# primary_LTC.net
KiCad netlist of a schematic drawn in Altium Designer
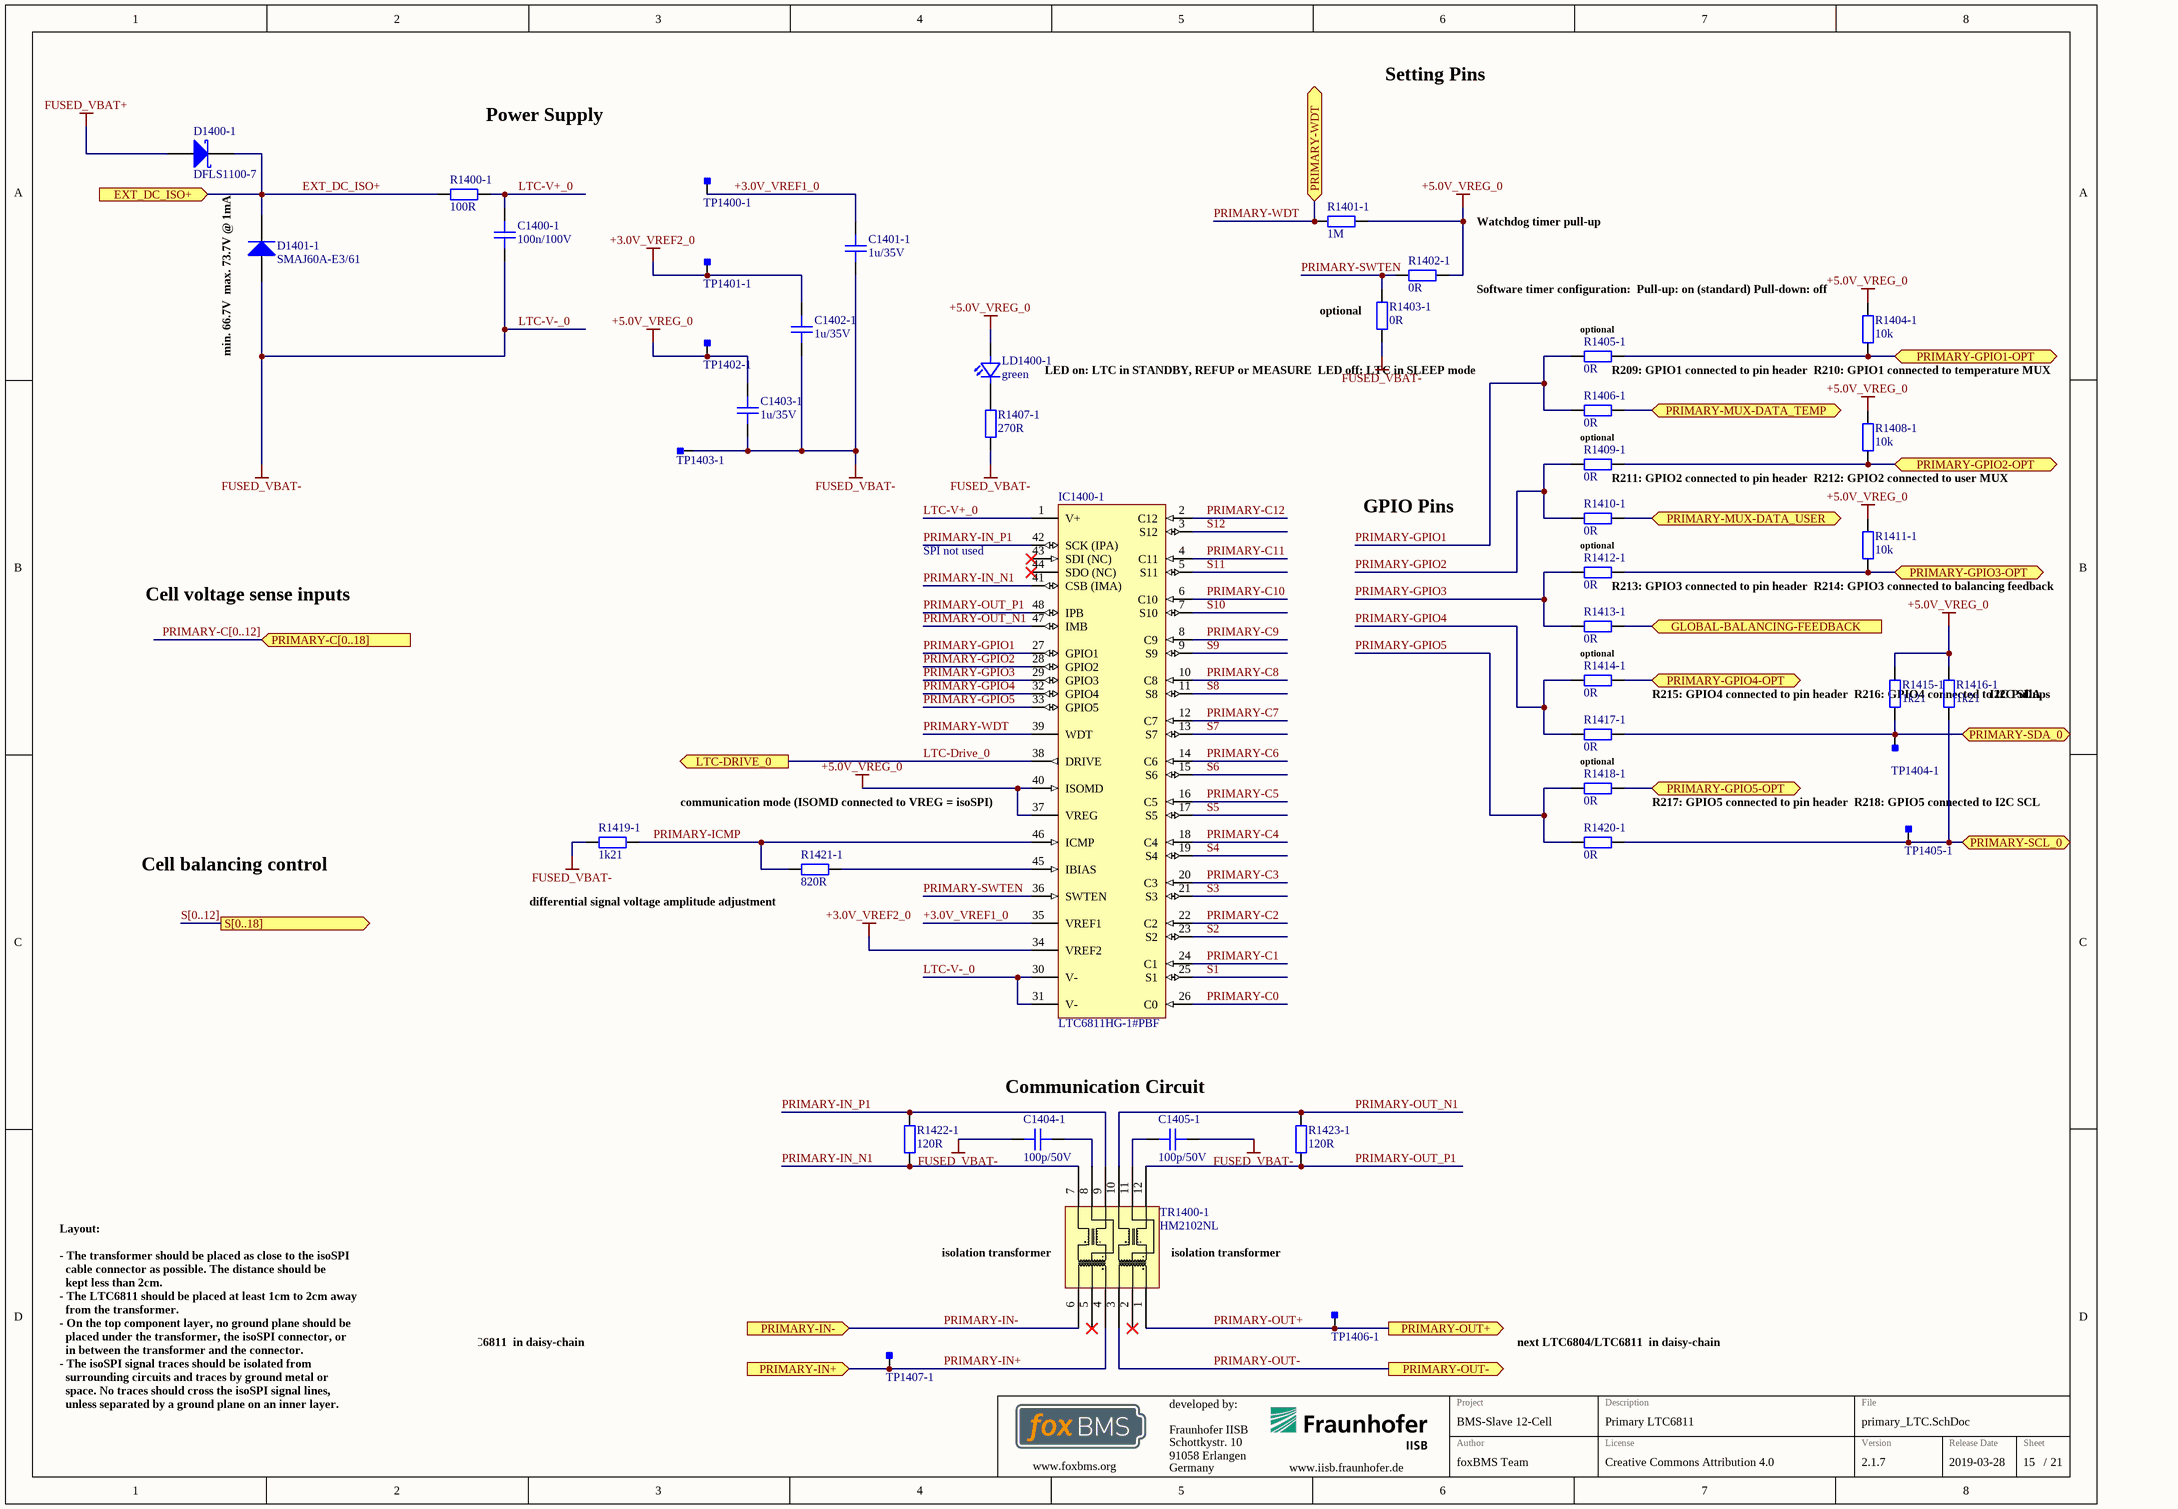
[diagram p0: primary_LTC.SchDoc]

(export (version "E")
  (design (tool "Eeschema 10.0.6"))
  (components
    (comp (ref "C1400-1")
      (value "100n/100V")
      (footprint "CAPC2012X14N")
      (description "MLCC")
      (fields (field (name "PART NUMBER") "gen_C_ceramic_100n_100V_X7R_0805"))
      (libsource (lib "OE750") (part "C"))
    )
    (comp (ref "C1401-1")
      (value "1u/35V")
      (footprint "CAPC1608X08N")
      (description "MLCC")
      (fields (field (name "PART NUMBER") "gen_C_ceramic_1u_35V_X7R_0603"))
      (libsource (lib "OE750") (part "C"))
    )
    (comp (ref "C1402-1")
      (value "1u/35V")
      (footprint "CAPC1608X08N")
      (description "MLCC")
      (fields (field (name "PART NUMBER") "gen_C_ceramic_1u_35V_X7R_0603"))
      (libsource (lib "OE750") (part "C"))
    )
    (comp (ref "C1403-1")
      (value "1u/35V")
      (footprint "CAPC1608X08N")
      (description "MLCC")
      (fields (field (name "PART NUMBER") "gen_C_ceramic_1u_35V_X7R_0603"))
      (libsource (lib "OE750") (part "C"))
    )
    (comp (ref "C1404-1")
      (value "100p/50V")
      (footprint "CAPC1608X08N")
      (description "MLCC")
      (fields (field (name "PART NUMBER") "gen_C_ceramic_100p_50V_C0G_0603"))
      (libsource (lib "OE750") (part "C"))
    )
    (comp (ref "C1405-1")
      (value "100p/50V")
      (footprint "CAPC1608X08N")
      (description "MLCC")
      (fields (field (name "PART NUMBER") "gen_C_ceramic_100p_50V_C0G_0603"))
      (libsource (lib "OE750") (part "C"))
    )
    (comp (ref "D1400-1")
      (value "DFLS1100-7")
      (footprint "DIOD-POWERDI123-2_V")
      (fields (field (name "MANUFACTURER") "Diodes Inc"))
      (libsource (lib "Altium Content Vault") (part "DSKY-AK-2"))
    )
    (comp (ref "D1401-1")
      (value "SMAJ60A-E3/61")
      (footprint "VISH-DO-214AC-2_N")
      (fields (field (name "MANUFACTURER") "Vishay Semiconductor"))
      (libsource (lib "Altium Content Vault") (part "VISH-K1A2-2"))
    )
    (comp (ref "IC1400-1")
      (value "LTC6811HG-1#PBF")
      (footprint "LT-G-48_L")
      (description "Multicell Battery Monitor, 60 V Vin MAX, 48-pin SOP (G-48), -40 to 125 degC, Pb-Free")
      (fields (field (name "MANUFACTURER") "Linear Technology"))
      (libsource (lib "OE750") (part "LTC6811HG-1#PBF"))
    )
    (comp (ref "LD1400-1")
      (value "green")
      (footprint "LEDC1608X07N")
      (description "LED")
      (fields (field (name "PART NUMBER") "gen_LED_0603_green"))
      (libsource (lib "OE750") (part "D_LED"))
    )
    (comp (ref "R1400-1")
      (value "100R")
      (footprint "RESC2012X05N")
      (description "SMD Resistor 100R 0805")
      (fields (field (name "PART NUMBER") "gen_R_100R_0805") (field (name "TOLERANCE") "1%"))
      (libsource (lib "OE750") (part "R"))
    )
    (comp (ref "R1401-1")
      (value "1M")
      (footprint "RESC1608X05N")
      (description "SMD Resistor 1M 0603")
      (fields (field (name "PART NUMBER") "gen_R_1M_0603") (field (name "TOLERANCE") "1%"))
      (libsource (lib "OE750") (part "R"))
    )
    (comp (ref "R1402-1")
      (value "0R")
      (footprint "RESC1608X05N")
      (description "SMD Resistor 0R 0603")
      (fields (field (name "PART NUMBER") "gen_R_0R_0603") (field (name "POWER") "0.1W"))
      (libsource (lib "OE750") (part "R"))
    )
    (comp (ref "R1403-1")
      (value "0R")
      (footprint "RESC1608X05N")
      (description "SMD Resistor 0R 0603")
      (fields (field (name "PART NUMBER") "gen_R_0R_0603") (field (name "POWER") "0.1W"))
      (libsource (lib "OE750") (part "R"))
    )
    (comp (ref "R1404-1")
      (value "10k")
      (footprint "RESC1608X05N")
      (description "SMD Resistor 10k 0603")
      (fields (field (name "PART NUMBER") "gen_R_10k_0603") (field (name "TOLERANCE") "1%"))
      (libsource (lib "OE750") (part "R"))
    )
    (comp (ref "R1405-1")
      (value "0R")
      (footprint "RESC1608X05N")
      (description "SMD Resistor 0R 0603")
      (fields (field (name "PART NUMBER") "gen_R_0R_0603") (field (name "POWER") "0.1W"))
      (libsource (lib "OE750") (part "R"))
    )
    (comp (ref "R1406-1")
      (value "0R")
      (footprint "RESC1608X05N")
      (description "SMD Resistor 0R 0603")
      (fields (field (name "PART NUMBER") "gen_R_0R_0603") (field (name "POWER") "0.1W"))
      (libsource (lib "OE750") (part "R"))
    )
    (comp (ref "R1407-1")
      (value "270R")
      (footprint "RESC1608X05N")
      (description "SMD Resistor 270R 0603")
      (fields (field (name "PART NUMBER") "gen_R_270R_0603") (field (name "TOLERANCE") "1%"))
      (libsource (lib "OE750") (part "R"))
    )
    (comp (ref "R1408-1")
      (value "10k")
      (footprint "RESC1608X05N")
      (description "SMD Resistor 10k 0603")
      (fields (field (name "PART NUMBER") "gen_R_10k_0603") (field (name "TOLERANCE") "1%"))
      (libsource (lib "OE750") (part "R"))
    )
    (comp (ref "R1409-1")
      (value "0R")
      (footprint "RESC1608X05N")
      (description "SMD Resistor 0R 0603")
      (fields (field (name "PART NUMBER") "gen_R_0R_0603") (field (name "POWER") "0.1W"))
      (libsource (lib "OE750") (part "R"))
    )
    (comp (ref "R1410-1")
      (value "0R")
      (footprint "RESC1608X05N")
      (description "SMD Resistor 0R 0603")
      (fields (field (name "PART NUMBER") "gen_R_0R_0603") (field (name "POWER") "0.1W"))
      (libsource (lib "OE750") (part "R"))
    )
    (comp (ref "R1411-1")
      (value "10k")
      (footprint "RESC1608X05N")
      (description "SMD Resistor 10k 0603")
      (fields (field (name "PART NUMBER") "gen_R_10k_0603") (field (name "TOLERANCE") "1%"))
      (libsource (lib "OE750") (part "R"))
    )
    (comp (ref "R1412-1")
      (value "0R")
      (footprint "RESC1608X05N")
      (description "SMD Resistor 0R 0603")
      (fields (field (name "PART NUMBER") "gen_R_0R_0603") (field (name "POWER") "0.1W"))
      (libsource (lib "OE750") (part "R"))
    )
    (comp (ref "R1413-1")
      (value "0R")
      (footprint "RESC1608X05N")
      (description "SMD Resistor 0R 0603")
      (fields (field (name "PART NUMBER") "gen_R_0R_0603") (field (name "POWER") "0.1W"))
      (libsource (lib "OE750") (part "R"))
    )
    (comp (ref "R1414-1")
      (value "0R")
      (footprint "RESC1608X05N")
      (description "SMD Resistor 0R 0603")
      (fields (field (name "PART NUMBER") "gen_R_0R_0603") (field (name "POWER") "0.1W"))
      (libsource (lib "OE750") (part "R"))
    )
    (comp (ref "R1415-1")
      (value "1k21")
      (footprint "RESC1608X05N")
      (description "SMD Resistor 1k21 0603")
      (fields (field (name "PART NUMBER") "gen_R_1k21_0603") (field (name "TOLERANCE") "1%"))
      (libsource (lib "OE750") (part "R"))
    )
    (comp (ref "R1416-1")
      (value "1k21")
      (footprint "RESC1608X05N")
      (description "SMD Resistor 1k21 0603")
      (fields (field (name "PART NUMBER") "gen_R_1k21_0603") (field (name "TOLERANCE") "1%"))
      (libsource (lib "OE750") (part "R"))
    )
    (comp (ref "R1417-1")
      (value "0R")
      (footprint "RESC1608X05N")
      (description "SMD Resistor 0R 0603")
      (fields (field (name "PART NUMBER") "gen_R_0R_0603") (field (name "POWER") "0.1W"))
      (libsource (lib "OE750") (part "R"))
    )
    (comp (ref "R1418-1")
      (value "0R")
      (footprint "RESC1608X05N")
      (description "SMD Resistor 0R 0603")
      (fields (field (name "PART NUMBER") "gen_R_0R_0603") (field (name "POWER") "0.1W"))
      (libsource (lib "OE750") (part "R"))
    )
    (comp (ref "R1419-1")
      (value "1k21")
      (footprint "RESC1608X05N")
      (description "SMD Resistor 1k21 0603")
      (fields (field (name "PART NUMBER") "gen_R_1k21_0603") (field (name "TOLERANCE") "1%"))
      (libsource (lib "OE750") (part "R"))
    )
    (comp (ref "R1420-1")
      (value "0R")
      (footprint "RESC1608X05N")
      (description "SMD Resistor 0R 0603")
      (fields (field (name "PART NUMBER") "gen_R_0R_0603") (field (name "POWER") "0.1W"))
      (libsource (lib "OE750") (part "R"))
    )
    (comp (ref "R1421-1")
      (value "820R")
      (footprint "RESC1608X05N")
      (description "SMD Resistor 820R 0603")
      (fields (field (name "PART NUMBER") "gen_R_820R_0603") (field (name "TOLERANCE") "1%"))
      (libsource (lib "OE750") (part "R"))
    )
    (comp (ref "R1422-1")
      (value "120R")
      (footprint "RESC1608X05N")
      (description "SMD Resistor 120R 0603")
      (fields (field (name "PART NUMBER") "gen_R_120R_0603") (field (name "TOLERANCE") "1%"))
      (libsource (lib "OE750") (part "R"))
    )
    (comp (ref "R1423-1")
      (value "120R")
      (footprint "RESC1608X05N")
      (description "SMD Resistor 120R 0603")
      (fields (field (name "PART NUMBER") "gen_R_120R_0603") (field (name "TOLERANCE") "1%"))
      (libsource (lib "OE750") (part "R"))
    )
    (comp (ref "TP1400-1")
      (value "Testpoint_Square")
      (footprint "Testpoint_S1")
      (description "Testpoint, square")
      (libsource (lib "OE750") (part "Testpoint_Square"))
    )
    (comp (ref "TP1401-1")
      (value "Testpoint_Square")
      (footprint "Testpoint_S1")
      (description "Testpoint, square")
      (libsource (lib "OE750") (part "Testpoint_Square"))
    )
    (comp (ref "TP1402-1")
      (value "Testpoint_Square")
      (footprint "Testpoint_S1")
      (description "Testpoint, square")
      (libsource (lib "OE750") (part "Testpoint_Square"))
    )
    (comp (ref "TP1403-1")
      (value "Testpoint_Square")
      (footprint "Testpoint_S1")
      (description "Testpoint, square")
      (libsource (lib "OE750") (part "Testpoint_Square"))
    )
    (comp (ref "TP1404-1")
      (value "Testpoint_Square")
      (footprint "Testpoint_S1")
      (description "Testpoint, square")
      (libsource (lib "OE750") (part "Testpoint_Square"))
    )
    (comp (ref "TP1405-1")
      (value "Testpoint_Square")
      (footprint "Testpoint_S1")
      (description "Testpoint, square")
      (libsource (lib "OE750") (part "Testpoint_Square"))
    )
    (comp (ref "TP1406-1")
      (value "Testpoint_Square")
      (footprint "Testpoint_S1")
      (description "Testpoint, square")
      (libsource (lib "OE750") (part "Testpoint_Square"))
    )
    (comp (ref "TP1407-1")
      (value "Testpoint_Square")
      (footprint "Testpoint_S1")
      (description "Testpoint, square")
      (libsource (lib "OE750") (part "Testpoint_Square"))
    )
    (comp (ref "TR1400-1")
      (value "HM2102NL")
      (footprint "HM2102NL")
      (description "Pulse HM2102NL BMS Transformer")
      (fields (field (name "MANUFACTURER") "Pulse"))
      (libsource (lib "OE750") (part "HM2102NL"))
    )
  )
  (nets
    (net (code "2") (name "+3.0V_VREF2_0") (class "Default")
      (node (ref "C1402-1") (pin "2") (pinfunction "2_2") (pintype "passive"))
      (node (ref "IC1400-1") (pin "34") (pinfunction "VREF2_34") (pintype "passive"))
      (node (ref "TP1401-1") (pin "1") (pinfunction "1_1") (pintype "passive"))
    )
    (net (code "3") (name "+5.0V_VREG_0") (class "Default")
      (node (ref "C1403-1") (pin "2") (pinfunction "2_2") (pintype "passive"))
      (node (ref "IC1400-1") (pin "37") (pinfunction "VREG_37") (pintype "power_in"))
      (node (ref "IC1400-1") (pin "40") (pinfunction "ISOMD_40") (pintype "input"))
      (node (ref "LD1400-1") (pin "2") (pinfunction "A_2") (pintype "passive"))
      (node (ref "R1401-1") (pin "2") (pinfunction "2_2") (pintype "passive"))
      (node (ref "R1402-1") (pin "2") (pinfunction "2_2") (pintype "passive"))
      (node (ref "R1404-1") (pin "2") (pinfunction "2_2") (pintype "passive"))
      (node (ref "R1408-1") (pin "2") (pinfunction "2_2") (pintype "passive"))
      (node (ref "R1411-1") (pin "2") (pinfunction "2_2") (pintype "passive"))
      (node (ref "R1415-1") (pin "2") (pinfunction "2_2") (pintype "passive"))
      (node (ref "R1416-1") (pin "2") (pinfunction "2_2") (pintype "passive"))
      (node (ref "TP1402-1") (pin "1") (pinfunction "1_1") (pintype "passive"))
    )
    (net (code "4") (name "/+3.0V_VREF1_0") (class "Default")
      (node (ref "C1401-1") (pin "2") (pinfunction "2_2") (pintype "passive"))
      (node (ref "IC1400-1") (pin "35") (pinfunction "VREF1_35") (pintype "passive"))
      (node (ref "TP1400-1") (pin "1") (pinfunction "1_1") (pintype "passive"))
    )
    (net (code "5") (name "/EXT_DC_ISO+") (class "Default")
      (node (ref "D1400-1") (pin "2") (pinfunction "K_2") (pintype "passive"))
      (node (ref "D1401-1") (pin "1") (pinfunction "K_1") (pintype "passive"))
      (node (ref "R1400-1") (pin "1") (pinfunction "1_1") (pintype "passive"))
    )
    (net (code "6") (name "/GLOBAL-BALANCING-FEEDBACK") (class "Default")
      (node (ref "R1413-1") (pin "1") (pinfunction "1_1") (pintype "passive"))
    )
    (net (code "7") (name "/LTC-Drive_0") (class "Default")
      (node (ref "IC1400-1") (pin "38") (pinfunction "DRIVE_38") (pintype "output"))
    )
    (net (code "8") (name "/LTC-V+_0") (class "Default")
      (node (ref "C1400-1") (pin "1") (pinfunction "1_1") (pintype "passive"))
      (node (ref "IC1400-1") (pin "1") (pinfunction "V+_1") (pintype "power_in"))
      (node (ref "R1400-1") (pin "2") (pinfunction "2_2") (pintype "passive"))
    )
    (net (code "9") (name "/PRIMARY-C0") (class "Default")
      (node (ref "IC1400-1") (pin "26") (pinfunction "C0_26") (pintype "input"))
    )
    (net (code "10") (name "/PRIMARY-C1") (class "Default")
      (node (ref "IC1400-1") (pin "24") (pinfunction "C1_24") (pintype "input"))
    )
    (net (code "11") (name "/PRIMARY-C2") (class "Default")
      (node (ref "IC1400-1") (pin "22") (pinfunction "C2_22") (pintype "input"))
    )
    (net (code "12") (name "/PRIMARY-C3") (class "Default")
      (node (ref "IC1400-1") (pin "20") (pinfunction "C3_20") (pintype "input"))
    )
    (net (code "13") (name "/PRIMARY-C4") (class "Default")
      (node (ref "IC1400-1") (pin "18") (pinfunction "C4_18") (pintype "input"))
    )
    (net (code "14") (name "/PRIMARY-C5") (class "Default")
      (node (ref "IC1400-1") (pin "16") (pinfunction "C5_16") (pintype "input"))
    )
    (net (code "15") (name "/PRIMARY-C6") (class "Default")
      (node (ref "IC1400-1") (pin "14") (pinfunction "C6_14") (pintype "input"))
    )
    (net (code "16") (name "/PRIMARY-C7") (class "Default")
      (node (ref "IC1400-1") (pin "12") (pinfunction "C7_12") (pintype "input"))
    )
    (net (code "17") (name "/PRIMARY-C8") (class "Default")
      (node (ref "IC1400-1") (pin "10") (pinfunction "C8_10") (pintype "input"))
    )
    (net (code "18") (name "/PRIMARY-C9") (class "Default")
      (node (ref "IC1400-1") (pin "8") (pinfunction "C9_8") (pintype "input"))
    )
    (net (code "19") (name "/PRIMARY-C10") (class "Default")
      (node (ref "IC1400-1") (pin "6") (pinfunction "C10_6") (pintype "input"))
    )
    (net (code "20") (name "/PRIMARY-C11") (class "Default")
      (node (ref "IC1400-1") (pin "4") (pinfunction "C11_4") (pintype "input"))
    )
    (net (code "21") (name "/PRIMARY-C12") (class "Default")
      (node (ref "IC1400-1") (pin "2") (pinfunction "C12_2") (pintype "input"))
    )
    (net (code "23") (name "/PRIMARY-GPIO1") (class "Default")
      (node (ref "IC1400-1") (pin "27") (pinfunction "GPIO1_27") (pintype "bidirectional"))
      (node (ref "R1405-1") (pin "2") (pinfunction "2_2") (pintype "passive"))
      (node (ref "R1406-1") (pin "2") (pinfunction "2_2") (pintype "passive"))
    )
    (net (code "24") (name "/PRIMARY-GPIO1-OPT") (class "Default")
      (node (ref "R1404-1") (pin "1") (pinfunction "1_1") (pintype "passive"))
      (node (ref "R1405-1") (pin "1") (pinfunction "1_1") (pintype "passive"))
    )
    (net (code "25") (name "/PRIMARY-GPIO2") (class "Default")
      (node (ref "IC1400-1") (pin "28") (pinfunction "GPIO2_28") (pintype "bidirectional"))
      (node (ref "R1409-1") (pin "2") (pinfunction "2_2") (pintype "passive"))
      (node (ref "R1410-1") (pin "2") (pinfunction "2_2") (pintype "passive"))
    )
    (net (code "26") (name "/PRIMARY-GPIO2-OPT") (class "Default")
      (node (ref "R1408-1") (pin "1") (pinfunction "1_1") (pintype "passive"))
      (node (ref "R1409-1") (pin "1") (pinfunction "1_1") (pintype "passive"))
    )
    (net (code "27") (name "/PRIMARY-GPIO3") (class "Default")
      (node (ref "IC1400-1") (pin "29") (pinfunction "GPIO3_29") (pintype "bidirectional"))
      (node (ref "R1412-1") (pin "2") (pinfunction "2_2") (pintype "passive"))
      (node (ref "R1413-1") (pin "2") (pinfunction "2_2") (pintype "passive"))
    )
    (net (code "28") (name "/PRIMARY-GPIO3-OPT") (class "Default")
      (node (ref "R1411-1") (pin "1") (pinfunction "1_1") (pintype "passive"))
      (node (ref "R1412-1") (pin "1") (pinfunction "1_1") (pintype "passive"))
    )
    (net (code "29") (name "/PRIMARY-GPIO4") (class "Default")
      (node (ref "IC1400-1") (pin "32") (pinfunction "GPIO4_32") (pintype "bidirectional"))
      (node (ref "R1414-1") (pin "2") (pinfunction "2_2") (pintype "passive"))
      (node (ref "R1417-1") (pin "2") (pinfunction "2_2") (pintype "passive"))
    )
    (net (code "30") (name "/PRIMARY-GPIO4-OPT") (class "Default")
      (node (ref "R1414-1") (pin "1") (pinfunction "1_1") (pintype "passive"))
    )
    (net (code "31") (name "/PRIMARY-GPIO5") (class "Default")
      (node (ref "IC1400-1") (pin "33") (pinfunction "GPIO5_33") (pintype "bidirectional"))
      (node (ref "R1418-1") (pin "2") (pinfunction "2_2") (pintype "passive"))
      (node (ref "R1420-1") (pin "2") (pinfunction "2_2") (pintype "passive"))
    )
    (net (code "32") (name "/PRIMARY-GPIO5-OPT") (class "Default")
      (node (ref "R1418-1") (pin "1") (pinfunction "1_1") (pintype "passive"))
    )
    (net (code "33") (name "/PRIMARY-ICMP") (class "Default")
      (node (ref "IC1400-1") (pin "46") (pinfunction "ICMP_46") (pintype "input"))
      (node (ref "R1419-1") (pin "2") (pinfunction "2_2") (pintype "passive"))
      (node (ref "R1421-1") (pin "1") (pinfunction "1_1") (pintype "passive"))
    )
    (net (code "34") (name "/PRIMARY-IN+") (class "Default")
      (node (ref "TP1407-1") (pin "1") (pinfunction "1_1") (pintype "passive"))
      (node (ref "TR1400-1") (pin "4") (pintype "passive"))
    )
    (net (code "35") (name "/PRIMARY-IN-") (class "Default")
      (node (ref "TR1400-1") (pin "6") (pintype "passive"))
    )
    (net (code "36") (name "/PRIMARY-IN_N1") (class "Default")
      (node (ref "IC1400-1") (pin "41") (pinfunction "CSB_(IMA)_41") (pintype "bidirectional"))
      (node (ref "R1422-1") (pin "2") (pinfunction "2_2") (pintype "passive"))
      (node (ref "TR1400-1") (pin "7") (pintype "passive"))
    )
    (net (code "37") (name "/PRIMARY-IN_P1") (class "Default")
      (node (ref "IC1400-1") (pin "42") (pinfunction "SCK_(IPA)_42") (pintype "bidirectional"))
      (node (ref "R1422-1") (pin "1") (pinfunction "1_1") (pintype "passive"))
      (node (ref "TR1400-1") (pin "9") (pintype "passive"))
    )
    (net (code "38") (name "/PRIMARY-MUX-DATA_TEMP") (class "Default")
      (node (ref "R1406-1") (pin "1") (pinfunction "1_1") (pintype "passive"))
    )
    (net (code "39") (name "/PRIMARY-MUX-DATA_USER") (class "Default")
      (node (ref "R1410-1") (pin "1") (pinfunction "1_1") (pintype "passive"))
    )
    (net (code "40") (name "/PRIMARY-OUT+") (class "Default")
      (node (ref "TP1406-1") (pin "1") (pinfunction "1_1") (pintype "passive"))
      (node (ref "TR1400-1") (pin "1") (pintype "passive"))
    )
    (net (code "41") (name "/PRIMARY-OUT-") (class "Default")
      (node (ref "TR1400-1") (pin "3") (pintype "passive"))
    )
    (net (code "42") (name "/PRIMARY-OUT_N1") (class "Default")
      (node (ref "IC1400-1") (pin "47") (pinfunction "IMB_47") (pintype "bidirectional"))
      (node (ref "R1423-1") (pin "2") (pinfunction "2_2") (pintype "passive"))
      (node (ref "TR1400-1") (pin "10") (pintype "passive"))
    )
    (net (code "43") (name "/PRIMARY-OUT_P1") (class "Default")
      (node (ref "IC1400-1") (pin "48") (pinfunction "IPB_48") (pintype "bidirectional"))
      (node (ref "R1423-1") (pin "1") (pinfunction "1_1") (pintype "passive"))
      (node (ref "TR1400-1") (pin "12") (pintype "passive"))
    )
    (net (code "44") (name "/PRIMARY-SCL_0") (class "Default")
      (node (ref "R1416-1") (pin "1") (pinfunction "1_1") (pintype "passive"))
      (node (ref "R1420-1") (pin "1") (pinfunction "1_1") (pintype "passive"))
      (node (ref "TP1405-1") (pin "1") (pinfunction "1_1") (pintype "passive"))
    )
    (net (code "45") (name "/PRIMARY-SDA_0") (class "Default")
      (node (ref "R1415-1") (pin "1") (pinfunction "1_1") (pintype "passive"))
      (node (ref "R1417-1") (pin "1") (pinfunction "1_1") (pintype "passive"))
      (node (ref "TP1404-1") (pin "1") (pinfunction "1_1") (pintype "passive"))
    )
    (net (code "46") (name "/PRIMARY-SWTEN") (class "Default")
      (node (ref "IC1400-1") (pin "36") (pinfunction "SWTEN_36") (pintype "input"))
      (node (ref "R1402-1") (pin "1") (pinfunction "1_1") (pintype "passive"))
      (node (ref "R1403-1") (pin "2") (pinfunction "2_2") (pintype "passive"))
    )
    (net (code "47") (name "/PRIMARY-WDT") (class "Default")
      (node (ref "IC1400-1") (pin "39") (pinfunction "WDT_39") (pintype "tri_state"))
      (node (ref "R1401-1") (pin "1") (pinfunction "1_1") (pintype "passive"))
    )
    (net (code "48") (name "/S1") (class "Default")
      (node (ref "IC1400-1") (pin "25") (pinfunction "S1_25") (pintype "bidirectional"))
    )
    (net (code "49") (name "/S2") (class "Default")
      (node (ref "IC1400-1") (pin "23") (pinfunction "S2_23") (pintype "bidirectional"))
    )
    (net (code "50") (name "/S3") (class "Default")
      (node (ref "IC1400-1") (pin "21") (pinfunction "S3_21") (pintype "bidirectional"))
    )
    (net (code "51") (name "/S4") (class "Default")
      (node (ref "IC1400-1") (pin "19") (pinfunction "S4_19") (pintype "bidirectional"))
    )
    (net (code "52") (name "/S5") (class "Default")
      (node (ref "IC1400-1") (pin "17") (pinfunction "S5_17") (pintype "bidirectional"))
    )
    (net (code "53") (name "/S6") (class "Default")
      (node (ref "IC1400-1") (pin "15") (pinfunction "S6_15") (pintype "bidirectional"))
    )
    (net (code "54") (name "/S7") (class "Default")
      (node (ref "IC1400-1") (pin "13") (pinfunction "S7_13") (pintype "bidirectional"))
    )
    (net (code "55") (name "/S8") (class "Default")
      (node (ref "IC1400-1") (pin "11") (pinfunction "S8_11") (pintype "bidirectional"))
    )
    (net (code "56") (name "/S9") (class "Default")
      (node (ref "IC1400-1") (pin "9") (pinfunction "S9_9") (pintype "bidirectional"))
    )
    (net (code "57") (name "/S10") (class "Default")
      (node (ref "IC1400-1") (pin "7") (pinfunction "S10_7") (pintype "bidirectional"))
    )
    (net (code "58") (name "/S11") (class "Default")
      (node (ref "IC1400-1") (pin "5") (pinfunction "S11_5") (pintype "bidirectional"))
    )
    (net (code "59") (name "/S12") (class "Default")
      (node (ref "IC1400-1") (pin "3") (pinfunction "S12_3") (pintype "bidirectional"))
    )
    (net (code "61") (name "FUSED_VBAT+") (class "Default")
      (node (ref "D1400-1") (pin "1") (pinfunction "A_1") (pintype "passive"))
    )
    (net (code "62") (name "FUSED_VBAT-") (class "Default")
      (node (ref "C1400-1") (pin "2") (pinfunction "2_2") (pintype "passive"))
      (node (ref "C1401-1") (pin "1") (pinfunction "1_1") (pintype "passive"))
      (node (ref "C1402-1") (pin "1") (pinfunction "1_1") (pintype "passive"))
      (node (ref "C1403-1") (pin "1") (pinfunction "1_1") (pintype "passive"))
      (node (ref "C1404-1") (pin "1") (pinfunction "1_1") (pintype "passive"))
      (node (ref "C1405-1") (pin "1") (pinfunction "1_1") (pintype "passive"))
      (node (ref "D1401-1") (pin "2") (pinfunction "A_2") (pintype "passive"))
      (node (ref "IC1400-1") (pin "30") (pinfunction "V-_30") (pintype "power_in"))
      (node (ref "IC1400-1") (pin "31") (pinfunction "V-_31") (pintype "power_in"))
      (node (ref "R1403-1") (pin "1") (pinfunction "1_1") (pintype "passive"))
      (node (ref "R1407-1") (pin "1") (pinfunction "1_1") (pintype "passive"))
      (node (ref "R1419-1") (pin "1") (pinfunction "1_1") (pintype "passive"))
      (node (ref "TP1403-1") (pin "1") (pinfunction "1_1") (pintype "passive"))
    )
    (net (code "63") (name "Net-(C1404-1-Pad2)") (class "Default")
      (node (ref "C1404-1") (pin "2") (pinfunction "2_2") (pintype "passive"))
      (node (ref "TR1400-1") (pin "8") (pintype "passive"))
    )
    (net (code "64") (name "Net-(C1405-1-Pad2)") (class "Default")
      (node (ref "C1405-1") (pin "2") (pinfunction "2_2") (pintype "passive"))
      (node (ref "TR1400-1") (pin "11") (pintype "passive"))
    )
    (net (code "65") (name "Net-(IC1400-1-IBIAS)") (class "Default")
      (node (ref "IC1400-1") (pin "45") (pinfunction "IBIAS_45") (pintype "input"))
      (node (ref "R1421-1") (pin "2") (pinfunction "2_2") (pintype "passive"))
    )
    (net (code "66") (name "Net-(LD1400-1-C)") (class "Default")
      (node (ref "LD1400-1") (pin "1") (pinfunction "C_1") (pintype "passive"))
      (node (ref "R1407-1") (pin "2") (pinfunction "2_2") (pintype "passive"))
    )
    (net (code "67") (name "unconnected-(IC1400-1-SDI_(NC)-Pad43)") (class "Default")
      (node (ref "IC1400-1") (pin "43") (pinfunction "SDI_(NC)_43") (pintype "input+no_connect"))
    )
    (net (code "68") (name "unconnected-(IC1400-1-SDO_(NC)-Pad44)") (class "Default")
      (node (ref "IC1400-1") (pin "44") (pinfunction "SDO_(NC)_44") (pintype "open_collector+no_connect"))
    )
    (net (code "69") (name "unconnected-(TR1400-1-Pad2)") (class "Default")
      (node (ref "TR1400-1") (pin "2") (pintype "passive+no_connect"))
    )
    (net (code "70") (name "unconnected-(TR1400-1-Pad5)") (class "Default")
      (node (ref "TR1400-1") (pin "5") (pintype "passive+no_connect"))
    )
  )
)
